# USB_-_C.net
KiCad netlist of a schematic drawn in Altium Designer
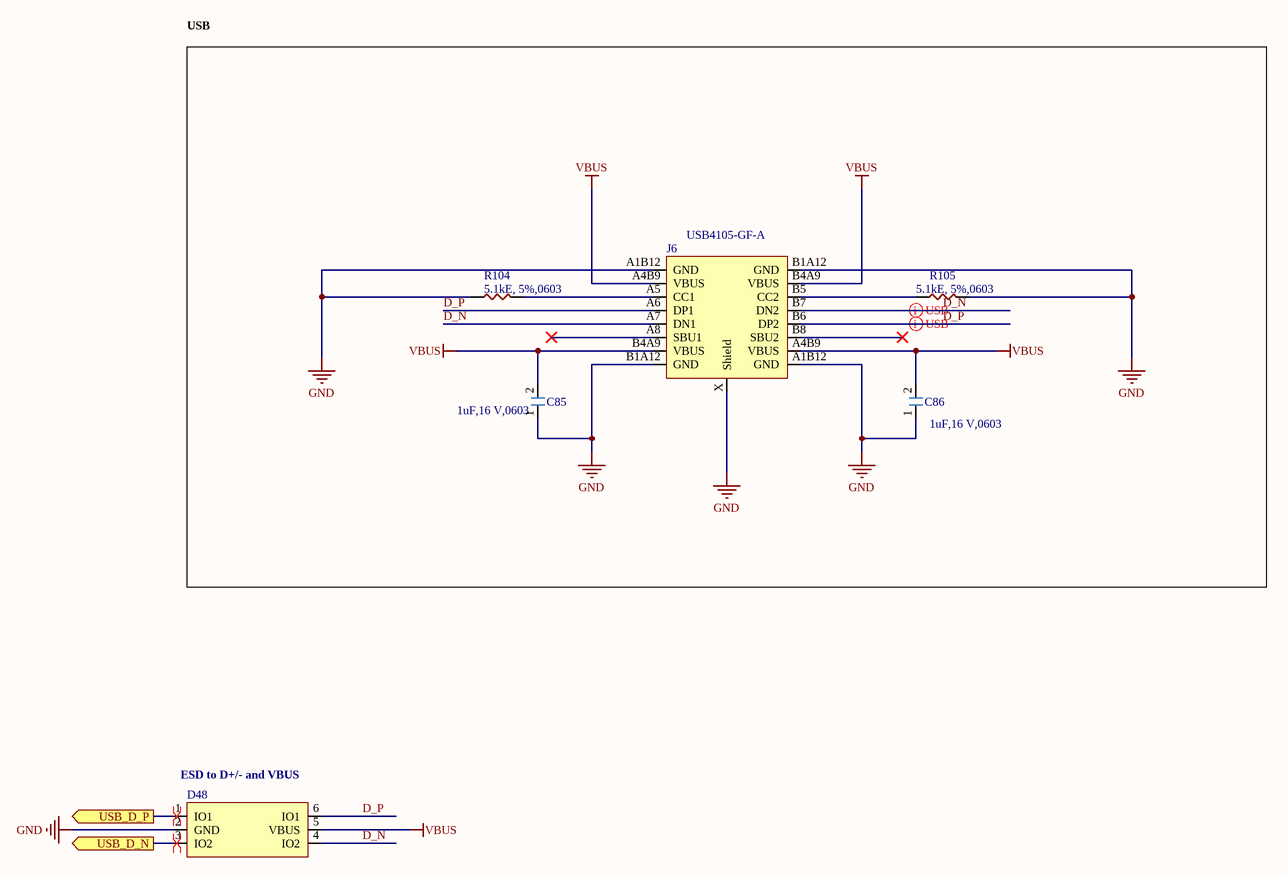
[diagram p0: USB - C.SchDoc]

(export (version "E")
  (design (tool "Eeschema 10.0.6"))
  (components
    (comp (ref "C85")
      (value "CGA3E1X7R1C105K080AC")
      (footprint "CAPC1608X05N 0603")
      (description "Multilayer Ceramic Capacitor, 1uF, 16V, ±10%,  X7R 0603 [1608 Metric]")
      (fields
        (field (name "MANUFACTURER") "TDK Corporation")
        (field (name "VOLTAGE") "16V")
        (field (name "VALUE DISPLAY") "1uF,16 V,0603")
      )
      (libsource (lib "BMS_V2.1_Adv") (part "Cap_CGA3E1X7R1C105K080AC"))
    )
    (comp (ref "C86")
      (value "CGA3E1X7R1C105K080AC")
      (footprint "CAPC1608X05N 0603")
      (description "Multilayer Ceramic Capacitor, 1uF, 16V, ±10%,  X7R 0603 [1608 Metric]")
      (fields
        (field (name "MANUFACTURER") "TDK Corporation")
        (field (name "VOLTAGE") "16V")
        (field (name "VALUE DISPLAY") "1uF,16 V,0603")
      )
      (libsource (lib "BMS_V2.1_Adv") (part "Cap_CGA3E1X7R1C105K080AC"))
    )
    (comp (ref "D48")
      (value "USBLC6-2SC6")
      (footprint "SOT95P280X145-6N")
      (description "17V Clamp 5A (8/20µs) Ipp Tvs Diode Surface Mount SOT-23-6")
      (fields (field (name "MANUFACTURER") "ST") (field (name "VOLTAGE") "5.25V"))
      (libsource (lib "BMS_V2.1_Adv") (part "Diode_TVS_USBLC6-2SC6"))
    )
    (comp (ref "J6")
      (value "USB4105-GF-A")
      (footprint "Con_USB4105-GF-A")
      (description "USB Type C 2.0 Connector")
      (fields (field (name "MANUFACTURER") "GCT"))
      (libsource (lib "BMS_V2.1_Adv") (part "Con_USB_USB4105-GF-A"))
    )
    (comp (ref "R104")
      (value "CRCW06035K10JNEA")
      (footprint "RESC1608X05N 0603")
      (description "SMD Chip Resistor, 5.1k Ohm, ± 5%, 250 mW, 0603 [1608 Metric], Thick Film, General Purpose")
      (fields
        (field (name "MANUFACTURER") "Vishay Dale")
        (field (name "POWER") "1/10W")
        (field (name "VALUE DISPLAY") "5.1kE, 5%,0603")
      )
      (libsource (lib "BMS_V2.1_Adv") (part "Res_CRCW06035K10JNEA"))
    )
    (comp (ref "R105")
      (value "CRCW06035K10JNEA")
      (footprint "RESC1608X05N 0603")
      (description "SMD Chip Resistor, 5.1k Ohm, ± 5%, 250 mW, 0603 [1608 Metric], Thick Film, General Purpose")
      (fields
        (field (name "MANUFACTURER") "Vishay Dale")
        (field (name "POWER") "1/10W")
        (field (name "VALUE DISPLAY") "5.1kE, 5%,0603")
      )
      (libsource (lib "BMS_V2.1_Adv") (part "Res_CRCW06035K10JNEA"))
    )
  )
  (nets
    (net (code "1") (name "/D_N") (class "Default")
      (node (ref "D48") (pin "4") (pinfunction "IO2_4") (pintype "passive"))
      (node (ref "J6") (pin "A7") (pinfunction "DN1_A7") (pintype "passive"))
      (node (ref "J6") (pin "B7") (pinfunction "DN2_B7") (pintype "passive"))
    )
    (net (code "2") (name "/D_P") (class "Default")
      (node (ref "D48") (pin "6") (pinfunction "IO1_6") (pintype "passive"))
      (node (ref "J6") (pin "A6") (pinfunction "DP1_A6") (pintype "passive"))
      (node (ref "J6") (pin "B6") (pinfunction "DP2_B6") (pintype "passive"))
    )
    (net (code "3") (name "/USB_D_N") (class "Default")
      (node (ref "D48") (pin "3") (pinfunction "IO2_3") (pintype "passive"))
    )
    (net (code "4") (name "/USB_D_P") (class "Default")
      (node (ref "D48") (pin "1") (pinfunction "IO1_1") (pintype "passive"))
    )
    (net (code "5") (name "GND") (class "Default")
      (node (ref "C85") (pin "1") (pinfunction "1_1") (pintype "passive"))
      (node (ref "C86") (pin "1") (pinfunction "1_1") (pintype "passive"))
      (node (ref "D48") (pin "2") (pinfunction "GND_2") (pintype "passive"))
      (node (ref "J6") (pin "A1B12") (pinfunction "GND_A1B12") (pintype "passive"))
      (node (ref "J6") (pin "B1A12") (pinfunction "GND_B1A12") (pintype "passive"))
      (node (ref "J6") (pin "X") (pinfunction "Shield_X") (pintype "passive"))
      (node (ref "R104") (pin "1") (pinfunction "1_1") (pintype "passive"))
      (node (ref "R105") (pin "2") (pinfunction "2_2") (pintype "passive"))
    )
    (net (code "6") (name "Net-(J6-CC1)") (class "Default")
      (node (ref "J6") (pin "A5") (pinfunction "CC1_A5") (pintype "passive"))
      (node (ref "R104") (pin "2") (pinfunction "2_2") (pintype "passive"))
    )
    (net (code "7") (name "Net-(J6-CC2)") (class "Default")
      (node (ref "J6") (pin "B5") (pinfunction "CC2_B5") (pintype "passive"))
      (node (ref "R105") (pin "1") (pinfunction "1_1") (pintype "passive"))
    )
    (net (code "8") (name "VBUS") (class "Default")
      (node (ref "C85") (pin "2") (pinfunction "2_2") (pintype "passive"))
      (node (ref "C86") (pin "2") (pinfunction "2_2") (pintype "passive"))
      (node (ref "D48") (pin "5") (pinfunction "VBUS_5") (pintype "passive"))
      (node (ref "J6") (pin "A4B9") (pinfunction "VBUS_A4B9") (pintype "passive"))
      (node (ref "J6") (pin "B4A9") (pinfunction "VBUS_B4A9") (pintype "passive"))
    )
    (net (code "9") (name "unconnected-(J6-SBU1-PadA8)") (class "Default")
      (node (ref "J6") (pin "A8") (pinfunction "SBU1_A8") (pintype "passive+no_connect"))
    )
    (net (code "10") (name "unconnected-(J6-SBU2-PadB8)") (class "Default")
      (node (ref "J6") (pin "B8") (pinfunction "SBU2_B8") (pintype "passive+no_connect"))
    )
  )
)
